# Lamp_Logic_Board_22_Power_3.net
KiCad netlist of a schematic drawn in EAGLE
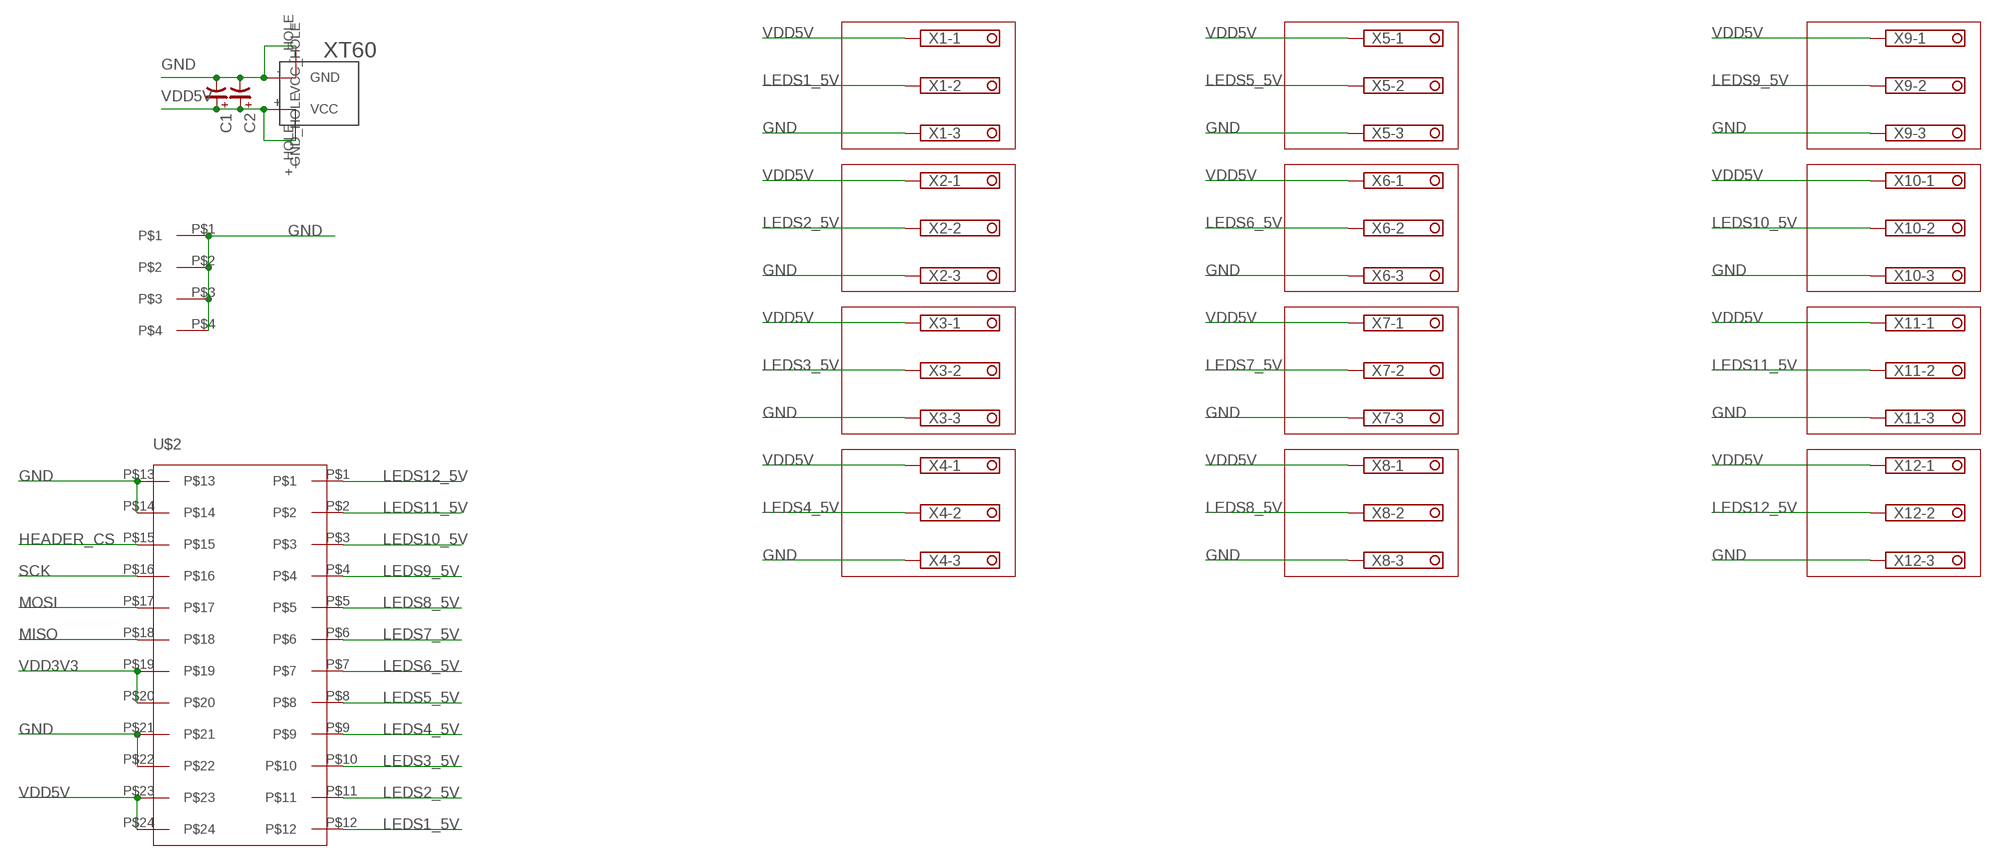
[diagram p0: schematic, sheet 1]

(export (version "E")
  (design (tool "Eeschema 10.0.6"))
  (components
    (comp (ref "C1")
      (value "CP_SV-G")
      (footprint "eagle-import:CSV-G")
      (libsource (lib "eagle-import") (part "CP_SV-G"))
    )
    (comp (ref "C2")
      (value "CP_SV-G")
      (footprint "eagle-import:CSV-G")
      (libsource (lib "eagle-import") (part "CP_SV-G"))
    )
    (comp (ref "U$1")
      (value "POWERBOARD_TEMPLATEPOWERBOARD_TEMPLATE")
      (footprint "eagle-import:4,PIECE")
      (libsource (lib "eagle-import") (part "POWERBOARD_TEMPLATEPOWERBOARD_TEMPLATE"))
    )
    (comp (ref "U$2")
      (value "MY_HEADER")
      (footprint "eagle-import:MY_HEADER")
      (libsource (lib "eagle-import") (part "MY_HEADER"))
    )
    (comp (ref "U$3")
      (value "XT60")
      (footprint "eagle-import:XT60")
      (libsource (lib "eagle-import") (part "XT60"))
    )
    (comp (ref "X1")
      (value "TERMINAL-BLOCK-3.5MM-3-PIN-LONG-PAD")
      (footprint "eagle-import:TERMINAL-BLOCK-3-PIN-3.5MM-LONG-PAD")
      (libsource (lib "eagle-import") (part "TERMINAL-BLOCK-3.5MM-3-PIN-LONG-PAD"))
    )
    (comp (ref "X2")
      (value "TERMINAL-BLOCK-3.5MM-3-PIN-LONG-PAD")
      (footprint "eagle-import:TERMINAL-BLOCK-3-PIN-3.5MM-LONG-PAD")
      (libsource (lib "eagle-import") (part "TERMINAL-BLOCK-3.5MM-3-PIN-LONG-PAD"))
    )
    (comp (ref "X3")
      (value "TERMINAL-BLOCK-3.5MM-3-PIN-LONG-PAD")
      (footprint "eagle-import:TERMINAL-BLOCK-3-PIN-3.5MM-LONG-PAD")
      (libsource (lib "eagle-import") (part "TERMINAL-BLOCK-3.5MM-3-PIN-LONG-PAD"))
    )
    (comp (ref "X4")
      (value "TERMINAL-BLOCK-3.5MM-3-PIN-LONG-PAD")
      (footprint "eagle-import:TERMINAL-BLOCK-3-PIN-3.5MM-LONG-PAD")
      (libsource (lib "eagle-import") (part "TERMINAL-BLOCK-3.5MM-3-PIN-LONG-PAD"))
    )
    (comp (ref "X5")
      (value "TERMINAL-BLOCK-3.5MM-3-PIN-LONG-PAD")
      (footprint "eagle-import:TERMINAL-BLOCK-3-PIN-3.5MM-LONG-PAD")
      (libsource (lib "eagle-import") (part "TERMINAL-BLOCK-3.5MM-3-PIN-LONG-PAD"))
    )
    (comp (ref "X6")
      (value "TERMINAL-BLOCK-3.5MM-3-PIN-LONG-PAD")
      (footprint "eagle-import:TERMINAL-BLOCK-3-PIN-3.5MM-LONG-PAD")
      (libsource (lib "eagle-import") (part "TERMINAL-BLOCK-3.5MM-3-PIN-LONG-PAD"))
    )
    (comp (ref "X7")
      (value "TERMINAL-BLOCK-3.5MM-3-PIN-LONG-PAD")
      (footprint "eagle-import:TERMINAL-BLOCK-3-PIN-3.5MM-LONG-PAD")
      (libsource (lib "eagle-import") (part "TERMINAL-BLOCK-3.5MM-3-PIN-LONG-PAD"))
    )
    (comp (ref "X8")
      (value "TERMINAL-BLOCK-3.5MM-3-PIN-LONG-PAD")
      (footprint "eagle-import:TERMINAL-BLOCK-3-PIN-3.5MM-LONG-PAD")
      (libsource (lib "eagle-import") (part "TERMINAL-BLOCK-3.5MM-3-PIN-LONG-PAD"))
    )
    (comp (ref "X9")
      (value "TERMINAL-BLOCK-3.5MM-3-PIN-LONG-PAD")
      (footprint "eagle-import:TERMINAL-BLOCK-3-PIN-3.5MM-LONG-PAD")
      (libsource (lib "eagle-import") (part "TERMINAL-BLOCK-3.5MM-3-PIN-LONG-PAD"))
    )
    (comp (ref "X10")
      (value "TERMINAL-BLOCK-3.5MM-3-PIN-LONG-PAD")
      (footprint "eagle-import:TERMINAL-BLOCK-3-PIN-3.5MM-LONG-PAD")
      (libsource (lib "eagle-import") (part "TERMINAL-BLOCK-3.5MM-3-PIN-LONG-PAD"))
    )
    (comp (ref "X11")
      (value "TERMINAL-BLOCK-3.5MM-3-PIN-LONG-PAD")
      (footprint "eagle-import:TERMINAL-BLOCK-3-PIN-3.5MM-LONG-PAD")
      (libsource (lib "eagle-import") (part "TERMINAL-BLOCK-3.5MM-3-PIN-LONG-PAD"))
    )
    (comp (ref "X12")
      (value "TERMINAL-BLOCK-3.5MM-3-PIN-LONG-PAD")
      (footprint "eagle-import:TERMINAL-BLOCK-3-PIN-3.5MM-LONG-PAD")
      (libsource (lib "eagle-import") (part "TERMINAL-BLOCK-3.5MM-3-PIN-LONG-PAD"))
    )
  )
  (nets
    (net (code "1") (name "/GND") (class "Default")
      (node (ref "C1") (pin "-") (pinfunction "-_-") (pintype "passive"))
      (node (ref "C2") (pin "-") (pinfunction "-_-") (pintype "passive"))
      (node (ref "U$1") (pin "P$1") (pinfunction "P$1_P$1") (pintype "bidirectional"))
      (node (ref "U$1") (pin "P$2") (pinfunction "P$2_P$2") (pintype "bidirectional"))
      (node (ref "U$1") (pin "P$3") (pinfunction "P$3_P$3") (pintype "bidirectional"))
      (node (ref "U$1") (pin "P$4") (pinfunction "P$4_P$4") (pintype "bidirectional"))
      (node (ref "U$2") (pin "P$13") (pinfunction "P$13_P$13") (pintype "bidirectional"))
      (node (ref "U$2") (pin "P$14") (pinfunction "P$14_P$14") (pintype "bidirectional"))
      (node (ref "U$2") (pin "P$21") (pinfunction "P$21_P$21") (pintype "bidirectional"))
      (node (ref "U$2") (pin "P$22") (pinfunction "P$22_P$22") (pintype "bidirectional"))
      (node (ref "U$3") (pin "-") (pinfunction "GND_-") (pintype "bidirectional"))
      (node (ref "U$3") (pin "-_HOLE") (pinfunction "GND_HOLE_-_HOLE") (pintype "bidirectional"))
      (node (ref "X1") (pin "3") (pinfunction "K_3") (pintype "passive"))
      (node (ref "X10") (pin "3") (pinfunction "K_3") (pintype "passive"))
      (node (ref "X11") (pin "3") (pinfunction "K_3") (pintype "passive"))
      (node (ref "X12") (pin "3") (pinfunction "K_3") (pintype "passive"))
      (node (ref "X2") (pin "3") (pinfunction "K_3") (pintype "passive"))
      (node (ref "X3") (pin "3") (pinfunction "K_3") (pintype "passive"))
      (node (ref "X4") (pin "3") (pinfunction "K_3") (pintype "passive"))
      (node (ref "X5") (pin "3") (pinfunction "K_3") (pintype "passive"))
      (node (ref "X6") (pin "3") (pinfunction "K_3") (pintype "passive"))
      (node (ref "X7") (pin "3") (pinfunction "K_3") (pintype "passive"))
      (node (ref "X8") (pin "3") (pinfunction "K_3") (pintype "passive"))
      (node (ref "X9") (pin "3") (pinfunction "K_3") (pintype "passive"))
    )
    (net (code "2") (name "/HEADER_CS") (class "Default")
      (node (ref "U$2") (pin "P$15") (pinfunction "P$15_P$15") (pintype "bidirectional"))
    )
    (net (code "3") (name "/LEDS1_5V") (class "Default")
      (node (ref "U$2") (pin "P$12") (pinfunction "P$12_P$12") (pintype "bidirectional"))
      (node (ref "X1") (pin "2") (pinfunction "K_2") (pintype "passive"))
    )
    (net (code "4") (name "/LEDS2_5V") (class "Default")
      (node (ref "U$2") (pin "P$11") (pinfunction "P$11_P$11") (pintype "bidirectional"))
      (node (ref "X2") (pin "2") (pinfunction "K_2") (pintype "passive"))
    )
    (net (code "5") (name "/LEDS3_5V") (class "Default")
      (node (ref "U$2") (pin "P$10") (pinfunction "P$10_P$10") (pintype "bidirectional"))
      (node (ref "X3") (pin "2") (pinfunction "K_2") (pintype "passive"))
    )
    (net (code "6") (name "/LEDS4_5V") (class "Default")
      (node (ref "U$2") (pin "P$9") (pinfunction "P$9_P$9") (pintype "bidirectional"))
      (node (ref "X4") (pin "2") (pinfunction "K_2") (pintype "passive"))
    )
    (net (code "7") (name "/LEDS5_5V") (class "Default")
      (node (ref "U$2") (pin "P$8") (pinfunction "P$8_P$8") (pintype "bidirectional"))
      (node (ref "X5") (pin "2") (pinfunction "K_2") (pintype "passive"))
    )
    (net (code "8") (name "/LEDS6_5V") (class "Default")
      (node (ref "U$2") (pin "P$7") (pinfunction "P$7_P$7") (pintype "bidirectional"))
      (node (ref "X6") (pin "2") (pinfunction "K_2") (pintype "passive"))
    )
    (net (code "9") (name "/LEDS7_5V") (class "Default")
      (node (ref "U$2") (pin "P$6") (pinfunction "P$6_P$6") (pintype "bidirectional"))
      (node (ref "X7") (pin "2") (pinfunction "K_2") (pintype "passive"))
    )
    (net (code "10") (name "/LEDS8_5V") (class "Default")
      (node (ref "U$2") (pin "P$5") (pinfunction "P$5_P$5") (pintype "bidirectional"))
      (node (ref "X8") (pin "2") (pinfunction "K_2") (pintype "passive"))
    )
    (net (code "11") (name "/LEDS9_5V") (class "Default")
      (node (ref "U$2") (pin "P$4") (pinfunction "P$4_P$4") (pintype "bidirectional"))
      (node (ref "X9") (pin "2") (pinfunction "K_2") (pintype "passive"))
    )
    (net (code "12") (name "/LEDS10_5V") (class "Default")
      (node (ref "U$2") (pin "P$3") (pinfunction "P$3_P$3") (pintype "bidirectional"))
      (node (ref "X10") (pin "2") (pinfunction "K_2") (pintype "passive"))
    )
    (net (code "13") (name "/LEDS11_5V") (class "Default")
      (node (ref "U$2") (pin "P$2") (pinfunction "P$2_P$2") (pintype "bidirectional"))
      (node (ref "X11") (pin "2") (pinfunction "K_2") (pintype "passive"))
    )
    (net (code "14") (name "/LEDS12_5V") (class "Default")
      (node (ref "U$2") (pin "P$1") (pinfunction "P$1_P$1") (pintype "bidirectional"))
      (node (ref "X12") (pin "2") (pinfunction "K_2") (pintype "passive"))
    )
    (net (code "15") (name "/MISO") (class "Default")
      (node (ref "U$2") (pin "P$18") (pinfunction "P$18_P$18") (pintype "bidirectional"))
    )
    (net (code "16") (name "/MOSI") (class "Default")
      (node (ref "U$2") (pin "P$17") (pinfunction "P$17_P$17") (pintype "bidirectional"))
    )
    (net (code "17") (name "/SCK") (class "Default")
      (node (ref "U$2") (pin "P$16") (pinfunction "P$16_P$16") (pintype "bidirectional"))
    )
    (net (code "18") (name "/VDD3V3") (class "Default")
      (node (ref "U$2") (pin "P$19") (pinfunction "P$19_P$19") (pintype "bidirectional"))
      (node (ref "U$2") (pin "P$20") (pinfunction "P$20_P$20") (pintype "bidirectional"))
    )
    (net (code "19") (name "/VDD5V") (class "Default")
      (node (ref "C1") (pin "+") (pinfunction "+_+") (pintype "passive"))
      (node (ref "C2") (pin "+") (pinfunction "+_+") (pintype "passive"))
      (node (ref "U$2") (pin "P$23") (pinfunction "P$23_P$23") (pintype "bidirectional"))
      (node (ref "U$2") (pin "P$24") (pinfunction "P$24_P$24") (pintype "bidirectional"))
      (node (ref "U$3") (pin "+") (pinfunction "VCC_+") (pintype "bidirectional"))
      (node (ref "U$3") (pin "+_HOLE") (pinfunction "VCC_HOLE_+_HOLE") (pintype "bidirectional"))
      (node (ref "X1") (pin "1") (pinfunction "K_1") (pintype "passive"))
      (node (ref "X10") (pin "1") (pinfunction "K_1") (pintype "passive"))
      (node (ref "X11") (pin "1") (pinfunction "K_1") (pintype "passive"))
      (node (ref "X12") (pin "1") (pinfunction "K_1") (pintype "passive"))
      (node (ref "X2") (pin "1") (pinfunction "K_1") (pintype "passive"))
      (node (ref "X3") (pin "1") (pinfunction "K_1") (pintype "passive"))
      (node (ref "X4") (pin "1") (pinfunction "K_1") (pintype "passive"))
      (node (ref "X5") (pin "1") (pinfunction "K_1") (pintype "passive"))
      (node (ref "X6") (pin "1") (pinfunction "K_1") (pintype "passive"))
      (node (ref "X7") (pin "1") (pinfunction "K_1") (pintype "passive"))
      (node (ref "X8") (pin "1") (pinfunction "K_1") (pintype "passive"))
      (node (ref "X9") (pin "1") (pinfunction "K_1") (pintype "passive"))
    )
  )
)
